# uArm_back_print.net
KiCad netlist of a schematic drawn in EAGLE
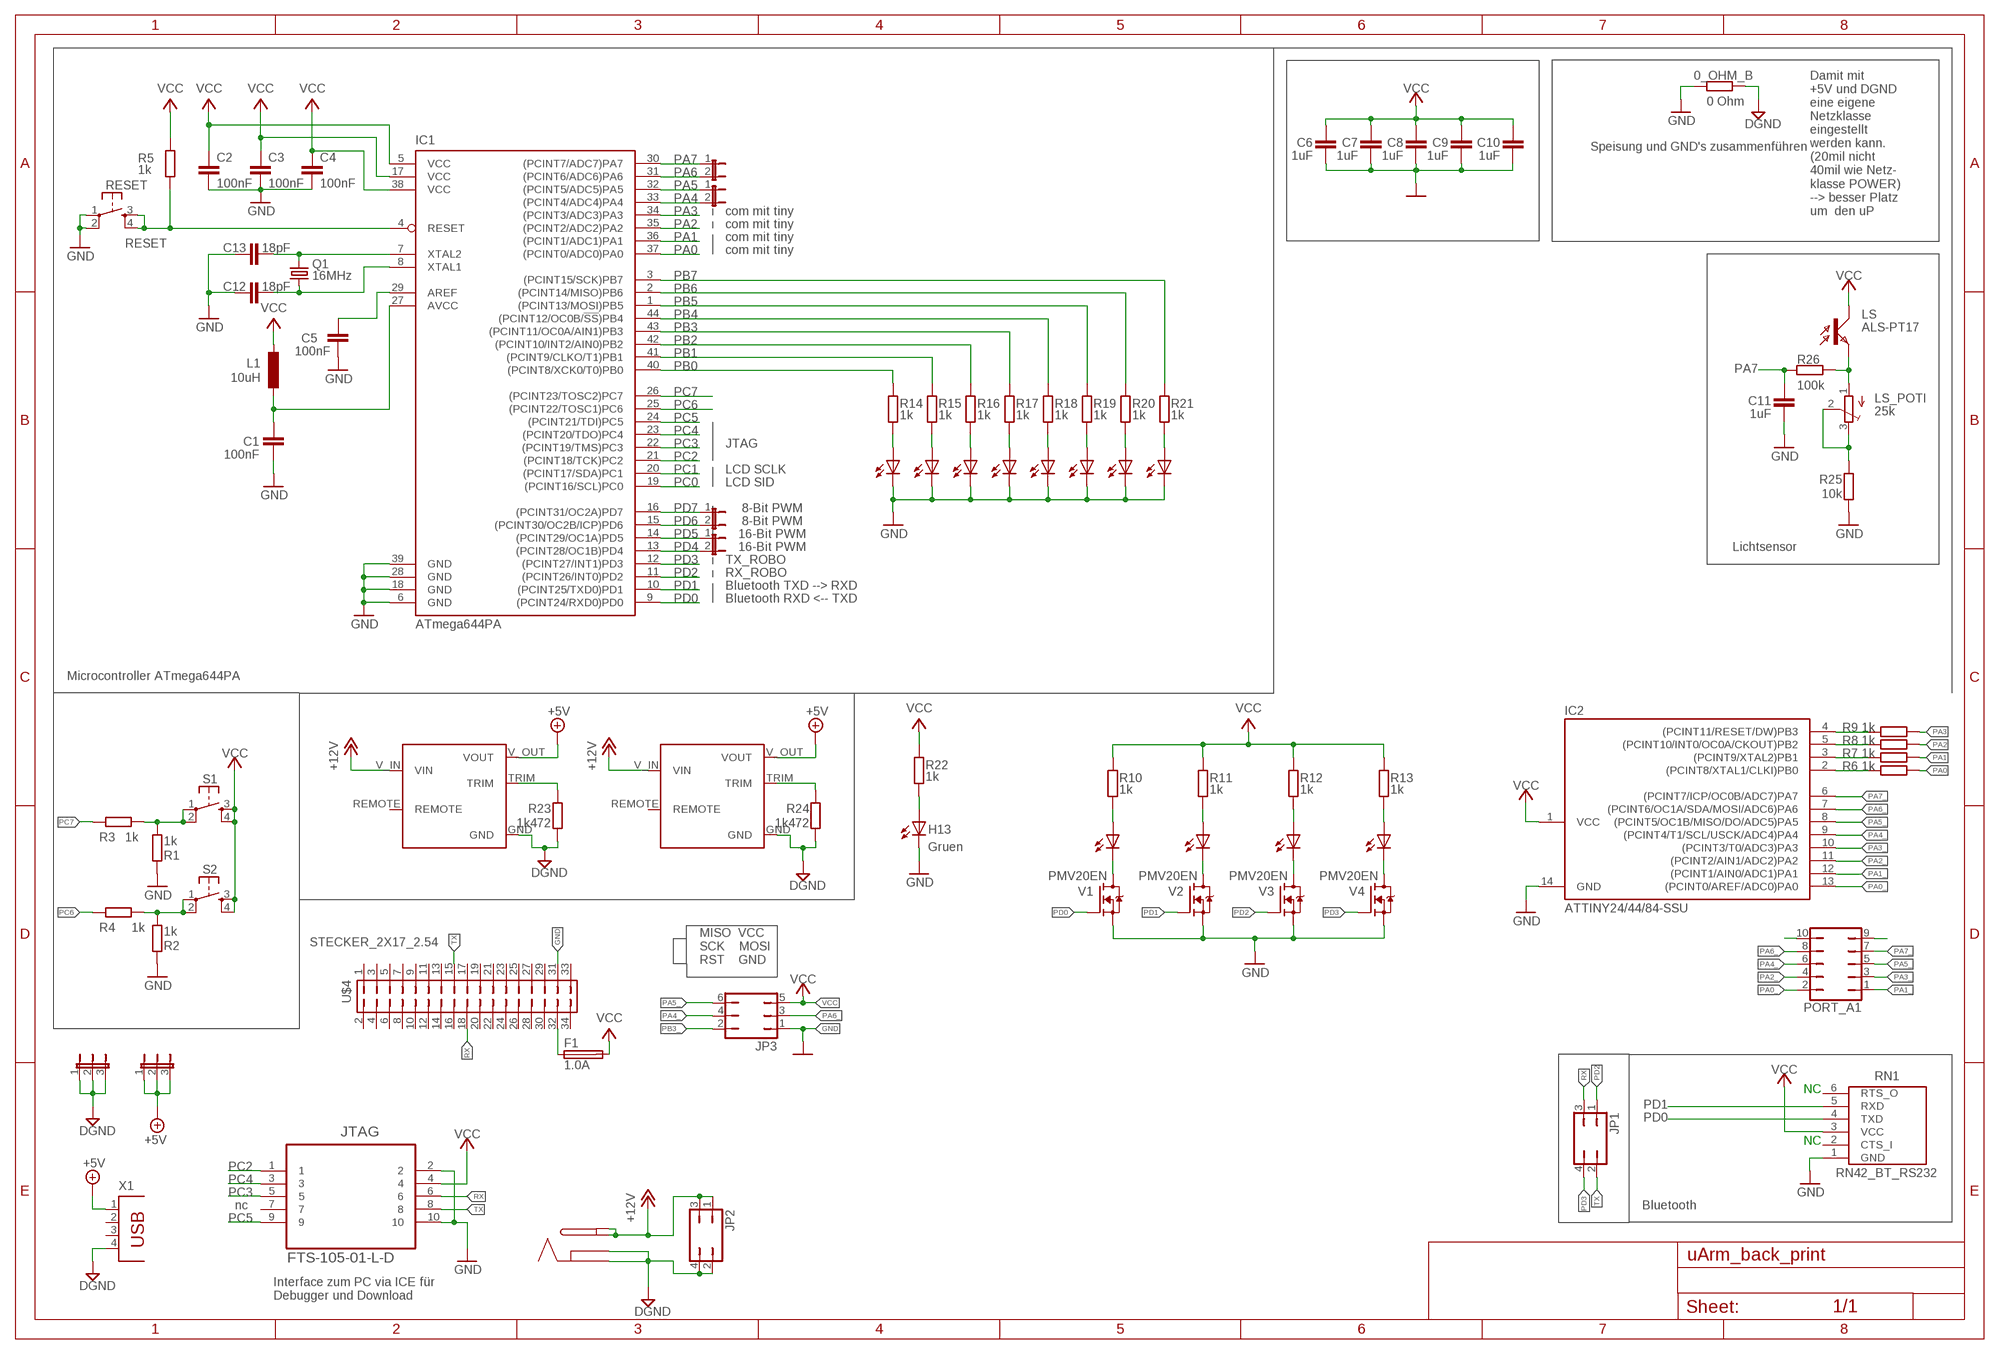
[diagram p0: schematic, sheet 1]

(export (version "E")
  (design (tool "Eeschema 10.0.6"))
  (components
    (comp (ref "0_OHM_B")
      (value "0 Ohm")
      (footprint "eagle-import:R0805")
      (libsource (lib "eagle-import") (part "R-EU_R0805"))
    )
    (comp (ref "C1")
      (value "100nF")
      (footprint "eagle-import:C0805")
      (libsource (lib "eagle-import") (part "C-EUC0805"))
    )
    (comp (ref "C2")
      (value "100nF")
      (footprint "eagle-import:C0805")
      (libsource (lib "eagle-import") (part "C-EUC0805"))
    )
    (comp (ref "C3")
      (value "100nF")
      (footprint "eagle-import:C0805")
      (libsource (lib "eagle-import") (part "C-EUC0805"))
    )
    (comp (ref "C4")
      (value "100nF")
      (footprint "eagle-import:C0805")
      (libsource (lib "eagle-import") (part "C-EUC0805"))
    )
    (comp (ref "C5")
      (value "100nF")
      (footprint "eagle-import:C0805")
      (libsource (lib "eagle-import") (part "C-EUC0805"))
    )
    (comp (ref "C6")
      (value "1uF")
      (footprint "eagle-import:C0805")
      (libsource (lib "eagle-import") (part "C-EUC0805"))
    )
    (comp (ref "C7")
      (value "1uF")
      (footprint "eagle-import:C0805")
      (libsource (lib "eagle-import") (part "C-EUC0805"))
    )
    (comp (ref "C8")
      (value "1uF")
      (footprint "eagle-import:C0805")
      (libsource (lib "eagle-import") (part "C-EUC0805"))
    )
    (comp (ref "C9")
      (value "1uF")
      (footprint "eagle-import:C0805")
      (libsource (lib "eagle-import") (part "C-EUC0805"))
    )
    (comp (ref "C10")
      (value "1uF")
      (footprint "eagle-import:C0805")
      (libsource (lib "eagle-import") (part "C-EUC0805"))
    )
    (comp (ref "C11")
      (value "1uF")
      (footprint "eagle-import:C0805")
      (libsource (lib "eagle-import") (part "C-EUC0805"))
    )
    (comp (ref "C12")
      (value "18pF")
      (footprint "eagle-import:C0805")
      (libsource (lib "eagle-import") (part "C-EUC0805"))
    )
    (comp (ref "C13")
      (value "18pF")
      (footprint "eagle-import:C0805")
      (libsource (lib "eagle-import") (part "C-EUC0805"))
    )
    (comp (ref "F1")
      (value "1.0A")
      (footprint "eagle-import:F1206")
      (libsource (lib "eagle-import") (part "195601206"))
    )
    (comp (ref "H1")
      (value "Gruen")
      (footprint "eagle-import:CHIPLED_1206")
      (libsource (lib "eagle-import") (part "LEDCHIPLED_1206"))
    )
    (comp (ref "H2")
      (value "Gruen")
      (footprint "eagle-import:CHIPLED_1206")
      (libsource (lib "eagle-import") (part "LEDCHIPLED_1206"))
    )
    (comp (ref "H3")
      (value "Gruen")
      (footprint "eagle-import:CHIPLED_1206")
      (libsource (lib "eagle-import") (part "LEDCHIPLED_1206"))
    )
    (comp (ref "H4")
      (value "Gruen")
      (footprint "eagle-import:CHIPLED_1206")
      (libsource (lib "eagle-import") (part "LEDCHIPLED_1206"))
    )
    (comp (ref "H5")
      (value "Gruen")
      (footprint "eagle-import:CHIPLED_1206")
      (libsource (lib "eagle-import") (part "LEDCHIPLED_1206"))
    )
    (comp (ref "H6")
      (value "Gruen")
      (footprint "eagle-import:CHIPLED_1206")
      (libsource (lib "eagle-import") (part "LEDCHIPLED_1206"))
    )
    (comp (ref "H7")
      (value "Gruen")
      (footprint "eagle-import:CHIPLED_1206")
      (libsource (lib "eagle-import") (part "LEDCHIPLED_1206"))
    )
    (comp (ref "H8")
      (value "Gruen")
      (footprint "eagle-import:CHIPLED_1206")
      (libsource (lib "eagle-import") (part "LEDCHIPLED_1206"))
    )
    (comp (ref "H9")
      (value "Gruen")
      (footprint "eagle-import:CHIPLED_1206")
      (libsource (lib "eagle-import") (part "LEDCHIPLED_1206"))
    )
    (comp (ref "H10")
      (value "Gruen")
      (footprint "eagle-import:CHIPLED_1206")
      (libsource (lib "eagle-import") (part "LEDCHIPLED_1206"))
    )
    (comp (ref "H11")
      (value "Gruen")
      (footprint "eagle-import:CHIPLED_1206")
      (libsource (lib "eagle-import") (part "LEDCHIPLED_1206"))
    )
    (comp (ref "H12")
      (value "Gruen")
      (footprint "eagle-import:CHIPLED_1206")
      (libsource (lib "eagle-import") (part "LEDCHIPLED_1206"))
    )
    (comp (ref "H13")
      (value "Gruen")
      (footprint "eagle-import:CHIPLED_1206")
      (libsource (lib "eagle-import") (part "LEDCHIPLED_1206"))
    )
    (comp (ref "IC1")
      (value "ATmega644PA")
      (footprint "eagle-import:TQFP44")
      (fields (field (name "MPN") "ATMEGA644PV-10AU"))
      (libsource (lib "eagle-import") (part "ATMEGA644A"))
    )
    (comp (ref "IC2")
      (value "ATTINY24/44/84-SSU")
      (footprint "eagle-import:SOIC14")
      (libsource (lib "eagle-import") (part "ATTINY24/44/84-SSU"))
    )
    (comp (ref "IC3")
      (value "DCDC")
      (footprint "eagle-import:1X2,3_2.54MM")
      (libsource (lib "eagle-import") (part "DCDC"))
    )
    (comp (ref "IC4")
      (value "DCDC")
      (footprint "eagle-import:1X2,3_2.54MM")
      (libsource (lib "eagle-import") (part "DCDC"))
    )
    (comp (ref "JP1")
      (value "JP2Q")
      (footprint "eagle-import:JP2Q")
      (libsource (lib "eagle-import") (part "JP2Q"))
    )
    (comp (ref "JP2")
      (value "JP2Q")
      (footprint "eagle-import:JP2Q")
      (libsource (lib "eagle-import") (part "JP2Q"))
    )
    (comp (ref "JP3")
      (value "JP3Q")
      (footprint "eagle-import:JP3Q")
      (libsource (lib "eagle-import") (part "JP3Q"))
    )
    (comp (ref "JP4")
      (value "JP1E")
      (footprint "eagle-import:JP1")
      (libsource (lib "eagle-import") (part "JP1E"))
    )
    (comp (ref "JP5")
      (value "JP1E")
      (footprint "eagle-import:JP1")
      (libsource (lib "eagle-import") (part "JP1E"))
    )
    (comp (ref "JP6")
      (value "JP2E")
      (footprint "eagle-import:JP2")
      (libsource (lib "eagle-import") (part "JP2E"))
    )
    (comp (ref "JP7")
      (value "JP2E")
      (footprint "eagle-import:JP2")
      (libsource (lib "eagle-import") (part "JP2E"))
    )
    (comp (ref "JP8")
      (value "JP1E")
      (footprint "eagle-import:JP1")
      (libsource (lib "eagle-import") (part "JP1E"))
    )
    (comp (ref "JP9")
      (value "JP1E")
      (footprint "eagle-import:JP1")
      (libsource (lib "eagle-import") (part "JP1E"))
    )
    (comp (ref "JTAG")
      (value "FTS-105-01-L-D")
      (footprint "eagle-import:SAMTEC_FTS-105-01-L-D")
      (libsource (lib "eagle-import") (part "FTS-105-01-L-D"))
    )
    (comp (ref "L1")
      (value "10uH")
      (footprint "eagle-import:L2825P")
      (libsource (lib "eagle-import") (part "L-EUL2825P"))
    )
    (comp (ref "LS")
      (value "ALS-PT17")
      (footprint "eagle-import:SOD232-W")
      (libsource (lib "eagle-import") (part "ALS-PT17-51C"))
    )
    (comp (ref "LS_POTI")
      (value "25k")
      (footprint "eagle-import:3223G")
      (libsource (lib "eagle-import") (part "TRIM_EU-3223G"))
    )
    (comp (ref "PORT_A1")
      (value "JP5Q")
      (footprint "eagle-import:JP5Q")
      (libsource (lib "eagle-import") (part "JP5Q"))
    )
    (comp (ref "Q1")
      (value "16MHz")
      (footprint "eagle-import:HC49UP")
      (libsource (lib "eagle-import") (part "CRYSTALHC49UP"))
    )
    (comp (ref "R1")
      (value "1k")
      (footprint "eagle-import:R0805")
      (libsource (lib "eagle-import") (part "R-EU_R0805"))
    )
    (comp (ref "R2")
      (value "1k")
      (footprint "eagle-import:R0805")
      (libsource (lib "eagle-import") (part "R-EU_R0805"))
    )
    (comp (ref "R3")
      (value "1k")
      (footprint "eagle-import:R0805")
      (libsource (lib "eagle-import") (part "R-EU_R0805"))
    )
    (comp (ref "R4")
      (value "1k")
      (footprint "eagle-import:R0805")
      (libsource (lib "eagle-import") (part "R-EU_R0805"))
    )
    (comp (ref "R5")
      (value "1k")
      (footprint "eagle-import:R0805")
      (libsource (lib "eagle-import") (part "R-EU_R0805"))
    )
    (comp (ref "R6")
      (value "1k")
      (footprint "eagle-import:R0805")
      (libsource (lib "eagle-import") (part "R-EU_R0805"))
    )
    (comp (ref "R7")
      (value "1k")
      (footprint "eagle-import:R0805")
      (libsource (lib "eagle-import") (part "R-EU_R0805"))
    )
    (comp (ref "R8")
      (value "1k")
      (footprint "eagle-import:R0805")
      (libsource (lib "eagle-import") (part "R-EU_R0805"))
    )
    (comp (ref "R9")
      (value "1k")
      (footprint "eagle-import:R0805")
      (libsource (lib "eagle-import") (part "R-EU_R0805"))
    )
    (comp (ref "R10")
      (value "1k")
      (footprint "eagle-import:R0805")
      (libsource (lib "eagle-import") (part "R-EU_R0805"))
    )
    (comp (ref "R11")
      (value "1k")
      (footprint "eagle-import:R0805")
      (libsource (lib "eagle-import") (part "R-EU_R0805"))
    )
    (comp (ref "R12")
      (value "1k")
      (footprint "eagle-import:R0805")
      (libsource (lib "eagle-import") (part "R-EU_R0805"))
    )
    (comp (ref "R13")
      (value "1k")
      (footprint "eagle-import:R0805")
      (libsource (lib "eagle-import") (part "R-EU_R0805"))
    )
    (comp (ref "R14")
      (value "1k")
      (footprint "eagle-import:R0805")
      (libsource (lib "eagle-import") (part "R-EU_R0805"))
    )
    (comp (ref "R15")
      (value "1k")
      (footprint "eagle-import:R0805")
      (libsource (lib "eagle-import") (part "R-EU_R0805"))
    )
    (comp (ref "R16")
      (value "1k")
      (footprint "eagle-import:R0805")
      (libsource (lib "eagle-import") (part "R-EU_R0805"))
    )
    (comp (ref "R17")
      (value "1k")
      (footprint "eagle-import:R0805")
      (libsource (lib "eagle-import") (part "R-EU_R0805"))
    )
    (comp (ref "R18")
      (value "1k")
      (footprint "eagle-import:R0805")
      (libsource (lib "eagle-import") (part "R-EU_R0805"))
    )
    (comp (ref "R19")
      (value "1k")
      (footprint "eagle-import:R0805")
      (libsource (lib "eagle-import") (part "R-EU_R0805"))
    )
    (comp (ref "R20")
      (value "1k")
      (footprint "eagle-import:R0805")
      (libsource (lib "eagle-import") (part "R-EU_R0805"))
    )
    (comp (ref "R21")
      (value "1k")
      (footprint "eagle-import:R0805")
      (libsource (lib "eagle-import") (part "R-EU_R0805"))
    )
    (comp (ref "R22")
      (value "1k")
      (footprint "eagle-import:R0805")
      (libsource (lib "eagle-import") (part "R-EU_R0805"))
    )
    (comp (ref "R23")
      (value "1k472")
      (footprint "eagle-import:R0805")
      (libsource (lib "eagle-import") (part "R-EU_R0805"))
    )
    (comp (ref "R24")
      (value "1k472")
      (footprint "eagle-import:R0805")
      (libsource (lib "eagle-import") (part "R-EU_R0805"))
    )
    (comp (ref "R25")
      (value "10k")
      (footprint "eagle-import:R0805")
      (libsource (lib "eagle-import") (part "R-EU_R0805"))
    )
    (comp (ref "R26")
      (value "100k")
      (footprint "eagle-import:R0805")
      (libsource (lib "eagle-import") (part "R-EU_R0805"))
    )
    (comp (ref "RESET")
      (value "TS42_4PAD")
      (footprint "eagle-import:TS42_4PAD")
      (libsource (lib "eagle-import") (part "TS42_4PAD"))
    )
    (comp (ref "RN1")
      (value "RN42_BT_RS232")
      (footprint "eagle-import:RN42BT_RS232")
      (libsource (lib "eagle-import") (part "RN42_BT_RS232"))
    )
    (comp (ref "S1")
      (value "TS42_4PAD")
      (footprint "eagle-import:TS42_4PAD")
      (libsource (lib "eagle-import") (part "TS42_4PAD"))
    )
    (comp (ref "S2")
      (value "TS42_4PAD")
      (footprint "eagle-import:TS42_4PAD")
      (libsource (lib "eagle-import") (part "TS42_4PAD"))
    )
    (comp (ref "U$1")
      (value "BUCHSE")
      (footprint "eagle-import:BUCHSE")
      (libsource (lib "eagle-import") (part "BUCHSE"))
    )
    (comp (ref "U$4")
      (value "STECKER_2X17_2.54")
      (footprint "eagle-import:2X17_2.54")
      (libsource (lib "eagle-import") (part "STECKER_2X17_2.54"))
    )
    (comp (ref "V1")
      (value "PMV20EN")
      (footprint "eagle-import:SOT23")
      (libsource (lib "eagle-import") (part "BSS138"))
    )
    (comp (ref "V2")
      (value "PMV20EN")
      (footprint "eagle-import:SOT23")
      (libsource (lib "eagle-import") (part "BSS138"))
    )
    (comp (ref "V3")
      (value "PMV20EN")
      (footprint "eagle-import:SOT23")
      (libsource (lib "eagle-import") (part "BSS138"))
    )
    (comp (ref "V4")
      (value "PMV20EN")
      (footprint "eagle-import:SOT23")
      (libsource (lib "eagle-import") (part "BSS138"))
    )
    (comp (ref "X1")
      (value "PN87520")
      (footprint "eagle-import:PN87520")
      (libsource (lib "eagle-import") (part "PN87520"))
    )
  )
  (nets
    (net (code "1") (name "+5V") (class "Default")
      (node (ref "IC3") (pin "V_OUT") (pinfunction "VOUT_V_OUT") (pintype "bidirectional"))
      (node (ref "IC4") (pin "V_OUT") (pinfunction "VOUT_V_OUT") (pintype "bidirectional"))
      (node (ref "JP6") (pin "1") (pinfunction "1_1") (pintype "passive"))
      (node (ref "JP6") (pin "2") (pinfunction "2_2") (pintype "passive"))
      (node (ref "JP6") (pin "3") (pinfunction "3_3") (pintype "passive"))
      (node (ref "X1") (pin "1") (pinfunction "1_1") (pintype "passive"))
    )
    (net (code "2") (name "+12V") (class "Default")
      (node (ref "IC3") (pin "V_IN") (pinfunction "VIN_V_IN") (pintype "bidirectional"))
      (node (ref "IC4") (pin "V_IN") (pinfunction "VIN_V_IN") (pintype "bidirectional"))
      (node (ref "JP2") (pin "1") (pinfunction "1_1") (pintype "passive"))
      (node (ref "JP2") (pin "3") (pinfunction "3_3") (pintype "passive"))
      (node (ref "U$1") (pin "3") (pinfunction "3_3") (pintype "bidirectional"))
      (node (ref "U$1") (pin "3.1") (pinfunction "3.1_3.1") (pintype "bidirectional"))
    )
    (net (code "3") (name "/PA4") (class "Default")
      (node (ref "IC1") (pin "33") (pinfunction "(PCINT4/ADC4)PA4_33") (pintype "bidirectional"))
      (node (ref "JP9") (pin "2") (pinfunction "2_2") (pintype "passive"))
    )
    (net (code "4") (name "/PA5") (class "Default")
      (node (ref "IC1") (pin "32") (pinfunction "(PCINT5/ADC5)PA5_32") (pintype "bidirectional"))
      (node (ref "JP9") (pin "1") (pinfunction "1_1") (pintype "passive"))
    )
    (net (code "5") (name "/PA6") (class "Default")
      (node (ref "IC1") (pin "31") (pinfunction "(PCINT6/ADC6)PA6_31") (pintype "bidirectional"))
      (node (ref "JP8") (pin "2") (pinfunction "2_2") (pintype "passive"))
    )
    (net (code "6") (name "/PA7") (class "Default")
      (node (ref "C11") (pin "2") (pinfunction "2_2") (pintype "passive"))
      (node (ref "IC1") (pin "30") (pinfunction "(PCINT7/ADC7)PA7_30") (pintype "bidirectional"))
      (node (ref "JP8") (pin "1") (pinfunction "1_1") (pintype "passive"))
      (node (ref "R26") (pin "1") (pinfunction "1_1") (pintype "passive"))
    )
    (net (code "7") (name "/PB0") (class "Default")
      (node (ref "IC1") (pin "40") (pinfunction "(PCINT8/XCK0/T0)PB0_40") (pintype "bidirectional"))
      (node (ref "R14") (pin "2") (pinfunction "2_2") (pintype "passive"))
    )
    (net (code "8") (name "/PB1") (class "Default")
      (node (ref "IC1") (pin "41") (pinfunction "(PCINT9/CLKO/T1)PB1_41") (pintype "bidirectional"))
      (node (ref "R15") (pin "2") (pinfunction "2_2") (pintype "passive"))
    )
    (net (code "9") (name "/PB2") (class "Default")
      (node (ref "IC1") (pin "42") (pinfunction "(PCINT10/INT2/AIN0)PB2_42") (pintype "bidirectional"))
      (node (ref "R16") (pin "2") (pinfunction "2_2") (pintype "passive"))
    )
    (net (code "10") (name "/PB3") (class "Default")
      (node (ref "IC1") (pin "43") (pinfunction "(PCINT11/OC0A/AIN1)PB3_43") (pintype "bidirectional"))
      (node (ref "R17") (pin "2") (pinfunction "2_2") (pintype "passive"))
    )
    (net (code "11") (name "/PB4") (class "Default")
      (node (ref "IC1") (pin "44") (pinfunction "(PCINT12/OC0B/~{SS})PB4_44") (pintype "bidirectional"))
      (node (ref "R18") (pin "2") (pinfunction "2_2") (pintype "passive"))
    )
    (net (code "12") (name "/PB5") (class "Default")
      (node (ref "IC1") (pin "1") (pinfunction "(PCINT13/MOSI)PB5_1") (pintype "bidirectional"))
      (node (ref "R19") (pin "2") (pinfunction "2_2") (pintype "passive"))
    )
    (net (code "13") (name "/PB6") (class "Default")
      (node (ref "IC1") (pin "2") (pinfunction "(PCINT14/MISO)PB6_2") (pintype "bidirectional"))
      (node (ref "R20") (pin "2") (pinfunction "2_2") (pintype "passive"))
    )
    (net (code "14") (name "/PB7") (class "Default")
      (node (ref "IC1") (pin "3") (pinfunction "(PCINT15/SCK)PB7_3") (pintype "bidirectional"))
      (node (ref "R21") (pin "2") (pinfunction "2_2") (pintype "passive"))
    )
    (net (code "15") (name "/PC0") (class "Default")
      (node (ref "IC1") (pin "19") (pinfunction "(PCINT16/SCL)PC0_19") (pintype "output"))
    )
    (net (code "16") (name "/PC1") (class "Default")
      (node (ref "IC1") (pin "20") (pinfunction "(PCINT17/SDA)PC1_20") (pintype "output"))
    )
    (net (code "17") (name "/PC2") (class "Default")
      (node (ref "IC1") (pin "21") (pinfunction "(PCINT18/TCK)PC2_21") (pintype "output"))
      (node (ref "JTAG") (pin "1") (pinfunction "1_1") (pintype "passive"))
    )
    (net (code "18") (name "/PC3") (class "Default")
      (node (ref "IC1") (pin "22") (pinfunction "(PCINT19/TMS)PC3_22") (pintype "output"))
      (node (ref "JTAG") (pin "5") (pinfunction "5_5") (pintype "passive"))
    )
    (net (code "19") (name "/PC4") (class "Default")
      (node (ref "IC1") (pin "23") (pinfunction "(PCINT20/TDO)PC4_23") (pintype "output"))
      (node (ref "JTAG") (pin "3") (pinfunction "3_3") (pintype "passive"))
    )
    (net (code "20") (name "/PC5") (class "Default")
      (node (ref "IC1") (pin "24") (pinfunction "(PCINT21/TDI)PC5_24") (pintype "output"))
      (node (ref "JTAG") (pin "9") (pinfunction "9_9") (pintype "passive"))
    )
    (net (code "21") (name "/PD4") (class "Default")
      (node (ref "IC1") (pin "13") (pinfunction "(PCINT28/OC1B)PD4_13") (pintype "bidirectional"))
      (node (ref "JP4") (pin "2") (pinfunction "2_2") (pintype "passive"))
    )
    (net (code "22") (name "/PD5") (class "Default")
      (node (ref "IC1") (pin "14") (pinfunction "(PCINT29/OC1A)PD5_14") (pintype "bidirectional"))
      (node (ref "JP4") (pin "1") (pinfunction "1_1") (pintype "passive"))
    )
    (net (code "23") (name "/PD6") (class "Default")
      (node (ref "IC1") (pin "15") (pinfunction "(PCINT30/OC2B/ICP)PD6_15") (pintype "bidirectional"))
      (node (ref "JP5") (pin "2") (pinfunction "2_2") (pintype "passive"))
    )
    (net (code "24") (name "/PD7") (class "Default")
      (node (ref "IC1") (pin "16") (pinfunction "(PCINT31/OC2A)PD7_16") (pintype "bidirectional"))
      (node (ref "JP5") (pin "1") (pinfunction "1_1") (pintype "passive"))
    )
    (net (code "25") (name "/RESET") (class "Default")
      (node (ref "IC1") (pin "4") (pinfunction "RESET_4") (pintype "input"))
      (node (ref "R5") (pin "1") (pinfunction "1_1") (pintype "passive"))
      (node (ref "RESET") (pin "3") (pinfunction "3_3") (pintype "passive"))
      (node (ref "RESET") (pin "4") (pinfunction "4_4") (pintype "passive"))
    )
    (net (code "26") (name "DGND") (class "Default")
      (node (ref "0_OHM_B") (pin "2") (pinfunction "2_2") (pintype "passive"))
      (node (ref "IC3") (pin "GND") (pinfunction "GND_GND") (pintype "bidirectional"))
      (node (ref "IC4") (pin "GND") (pinfunction "GND_GND") (pintype "bidirectional"))
      (node (ref "JP2") (pin "2") (pinfunction "2_2") (pintype "passive"))
      (node (ref "JP2") (pin "4") (pinfunction "4_4") (pintype "passive"))
      (node (ref "JP7") (pin "1") (pinfunction "1_1") (pintype "passive"))
      (node (ref "JP7") (pin "2") (pinfunction "2_2") (pintype "passive"))
      (node (ref "JP7") (pin "3") (pinfunction "3_3") (pintype "passive"))
      (node (ref "R23") (pin "1") (pinfunction "1_1") (pintype "passive"))
      (node (ref "R24") (pin "1") (pinfunction "1_1") (pintype "passive"))
      (node (ref "U$1") (pin "1") (pinfunction "1_1") (pintype "bidirectional"))
      (node (ref "U$1") (pin "2") (pinfunction "2_2") (pintype "bidirectional"))
      (node (ref "X1") (pin "4") (pinfunction "4_4") (pintype "passive"))
    )
    (net (code "27") (name "GND") (class "Default")
      (node (ref "0_OHM_B") (pin "1") (pinfunction "1_1") (pintype "passive"))
      (node (ref "C1") (pin "1") (pinfunction "1_1") (pintype "passive"))
      (node (ref "C10") (pin "1") (pinfunction "1_1") (pintype "passive"))
      (node (ref "C11") (pin "1") (pinfunction "1_1") (pintype "passive"))
      (node (ref "C12") (pin "2") (pinfunction "2_2") (pintype "passive"))
      (node (ref "C13") (pin "1") (pinfunction "1_1") (pintype "passive"))
      (node (ref "C2") (pin "2") (pinfunction "2_2") (pintype "passive"))
      (node (ref "C3") (pin "2") (pinfunction "2_2") (pintype "passive"))
      (node (ref "C4") (pin "2") (pinfunction "2_2") (pintype "passive"))
      (node (ref "C5") (pin "1") (pinfunction "1_1") (pintype "passive"))
      (node (ref "C6") (pin "1") (pinfunction "1_1") (pintype "passive"))
      (node (ref "C7") (pin "1") (pinfunction "1_1") (pintype "passive"))
      (node (ref "C8") (pin "1") (pinfunction "1_1") (pintype "passive"))
      (node (ref "C9") (pin "1") (pinfunction "1_1") (pintype "passive"))
      (node (ref "H1") (pin "C") (pinfunction "C_C") (pintype "passive"))
      (node (ref "H13") (pin "C") (pinfunction "C_C") (pintype "passive"))
      (node (ref "H2") (pin "C") (pinfunction "C_C") (pintype "passive"))
      (node (ref "H3") (pin "C") (pinfunction "C_C") (pintype "passive"))
      (node (ref "H4") (pin "C") (pinfunction "C_C") (pintype "passive"))
      (node (ref "H5") (pin "C") (pinfunction "C_C") (pintype "passive"))
      (node (ref "H6") (pin "C") (pinfunction "C_C") (pintype "passive"))
      (node (ref "H7") (pin "C") (pinfunction "C_C") (pintype "passive"))
      (node (ref "H8") (pin "C") (pinfunction "C_C") (pintype "passive"))
      (node (ref "IC1") (pin "18") (pinfunction "GND_18") (pintype "power_in"))
      (node (ref "IC1") (pin "28") (pinfunction "GND_28") (pintype "power_in"))
      (node (ref "IC1") (pin "39") (pinfunction "GND_39") (pintype "power_in"))
      (node (ref "IC1") (pin "6") (pinfunction "GND_6") (pintype "power_in"))
      (node (ref "IC2") (pin "14") (pinfunction "GND_14") (pintype "power_in"))
      (node (ref "JP3") (pin "1") (pinfunction "1_1") (pintype "passive"))
      (node (ref "JTAG") (pin "10") (pinfunction "10_10") (pintype "passive"))
      (node (ref "JTAG") (pin "2") (pinfunction "2_2") (pintype "passive"))
      (node (ref "R1") (pin "1") (pinfunction "1_1") (pintype "passive"))
      (node (ref "R2") (pin "1") (pinfunction "1_1") (pintype "passive"))
      (node (ref "R25") (pin "1") (pinfunction "1_1") (pintype "passive"))
      (node (ref "RESET") (pin "1") (pinfunction "1_1") (pintype "passive"))
      (node (ref "RESET") (pin "2") (pinfunction "2_2") (pintype "passive"))
      (node (ref "RN1") (pin "1") (pinfunction "GND_1") (pintype "bidirectional"))
      (node (ref "U$4") (pin "31") (pinfunction "31_31") (pintype "passive"))
      (node (ref "V1") (pin "2") (pinfunction "S_2") (pintype "passive"))
      (node (ref "V2") (pin "2") (pinfunction "S_2") (pintype "passive"))
      (node (ref "V3") (pin "2") (pinfunction "S_2") (pintype "passive"))
      (node (ref "V4") (pin "2") (pinfunction "S_2") (pintype "passive"))
    )
    (net (code "28") (name "Net-(F1-Pad1)") (class "Default")
      (node (ref "F1") (pin "1") (pinfunction "1_1") (pintype "passive"))
      (node (ref "U$4") (pin "32") (pinfunction "32_32") (pintype "passive"))
    )
    (net (code "29") (name "Net-(H1-PadA)") (class "Default")
      (node (ref "H1") (pin "A") (pinfunction "A_A") (pintype "passive"))
      (node (ref "R14") (pin "1") (pinfunction "1_1") (pintype "passive"))
    )
    (net (code "30") (name "Net-(H2-PadA)") (class "Default")
      (node (ref "H2") (pin "A") (pinfunction "A_A") (pintype "passive"))
      (node (ref "R15") (pin "1") (pinfunction "1_1") (pintype "passive"))
    )
    (net (code "31") (name "Net-(H3-PadA)") (class "Default")
      (node (ref "H3") (pin "A") (pinfunction "A_A") (pintype "passive"))
      (node (ref "R16") (pin "1") (pinfunction "1_1") (pintype "passive"))
    )
    (net (code "32") (name "Net-(H4-PadA)") (class "Default")
      (node (ref "H4") (pin "A") (pinfunction "A_A") (pintype "passive"))
      (node (ref "R17") (pin "1") (pinfunction "1_1") (pintype "passive"))
    )
    (net (code "33") (name "Net-(H5-PadA)") (class "Default")
      (node (ref "H5") (pin "A") (pinfunction "A_A") (pintype "passive"))
      (node (ref "R18") (pin "1") (pinfunction "1_1") (pintype "passive"))
    )
    (net (code "34") (name "Net-(H6-PadA)") (class "Default")
      (node (ref "H6") (pin "A") (pinfunction "A_A") (pintype "passive"))
      (node (ref "R19") (pin "1") (pinfunction "1_1") (pintype "passive"))
    )
    (net (code "35") (name "Net-(H7-PadA)") (class "Default")
      (node (ref "H7") (pin "A") (pinfunction "A_A") (pintype "passive"))
      (node (ref "R20") (pin "1") (pinfunction "1_1") (pintype "passive"))
    )
    (net (code "36") (name "Net-(H8-PadA)") (class "Default")
      (node (ref "H8") (pin "A") (pinfunction "A_A") (pintype "passive"))
      (node (ref "R21") (pin "1") (pinfunction "1_1") (pintype "passive"))
    )
    (net (code "37") (name "Net-(H9-PadA)") (class "Default")
      (node (ref "H9") (pin "A") (pinfunction "A_A") (pintype "passive"))
      (node (ref "R10") (pin "1") (pinfunction "1_1") (pintype "passive"))
    )
    (net (code "38") (name "Net-(H10-PadA)") (class "Default")
      (node (ref "H10") (pin "A") (pinfunction "A_A") (pintype "passive"))
      (node (ref "R11") (pin "1") (pinfunction "1_1") (pintype "passive"))
    )
    (net (code "39") (name "Net-(H11-PadA)") (class "Default")
      (node (ref "H11") (pin "A") (pinfunction "A_A") (pintype "passive"))
      (node (ref "R12") (pin "1") (pinfunction "1_1") (pintype "passive"))
    )
    (net (code "40") (name "Net-(H12-PadA)") (class "Default")
      (node (ref "H12") (pin "A") (pinfunction "A_A") (pintype "passive"))
      (node (ref "R13") (pin "1") (pinfunction "1_1") (pintype "passive"))
    )
    (net (code "41") (name "Net-(H13-PadA)") (class "Default")
      (node (ref "H13") (pin "A") (pinfunction "A_A") (pintype "passive"))
      (node (ref "R22") (pin "1") (pinfunction "1_1") (pintype "passive"))
    )
    (net (code "42") (name "Net-(IC1-AREF)") (class "Default")
      (node (ref "C5") (pin "2") (pinfunction "2_2") (pintype "passive"))
      (node (ref "IC1") (pin "29") (pinfunction "AREF_29") (pintype "passive"))
    )
    (net (code "43") (name "Net-(IC1-AVCC)") (class "Default")
      (node (ref "C1") (pin "2") (pinfunction "2_2") (pintype "passive"))
      (node (ref "IC1") (pin "27") (pinfunction "AVCC_27") (pintype "passive"))
      (node (ref "L1") (pin "2") (pinfunction "2_2") (pintype "passive"))
    )
    (net (code "44") (name "Net-(IC1-XTAL1)") (class "Default")
      (node (ref "C12") (pin "1") (pinfunction "1_1") (pintype "passive"))
      (node (ref "IC1") (pin "8") (pinfunction "XTAL1_8") (pintype "bidirectional"))
      (node (ref "Q1") (pin "1") (pinfunction "1_1") (pintype "passive"))
    )
    (net (code "45") (name "Net-(IC1-XTAL2)") (class "Default")
      (node (ref "C13") (pin "2") (pinfunction "2_2") (pintype "passive"))
      (node (ref "IC1") (pin "7") (pinfunction "XTAL2_7") (pintype "bidirectional"))
      (node (ref "Q1") (pin "2") (pinfunction "2_2") (pintype "passive"))
    )
    (net (code "46") (name "Net-(IC2-(PCINT8{slash}XTAL1{slash}CLKI)PB0)") (class "Default")
      (node (ref "IC2") (pin "2") (pinfunction "(PCINT8/XTAL1/CLKI)PB0_2") (pintype "bidirectional"))
      (node (ref "R6") (pin "2") (pinfunction "2_2") (pintype "passive"))
    )
    (net (code "47") (name "Net-(IC2-(PCINT9{slash}XTAL2)PB1)") (class "Default")
      (node (ref "IC2") (pin "3") (pinfunction "(PCINT9/XTAL2)PB1_3") (pintype "bidirectional"))
      (node (ref "R7") (pin "2") (pinfunction "2_2") (pintype "passive"))
    )
    (net (code "48") (name "Net-(IC2-(PCINT10{slash}INT0{slash}OC0A{slash}CKOUT)PB2)") (class "Default")
      (node (ref "IC2") (pin "5") (pinfunction "(PCINT10/INT0/OC0A/CKOUT)PB2_5") (pintype "bidirectional"))
      (node (ref "R8") (pin "2") (pinfunction "2_2") (pintype "passive"))
    )
    (net (code "49") (name "Net-(IC3-PadTRIM)") (class "Default")
      (node (ref "IC3") (pin "TRIM") (pinfunction "TRIM_TRIM") (pintype "bidirectional"))
      (node (ref "R23") (pin "2") (pinfunction "2_2") (pintype "passive"))
    )
    (net (code "50") (name "Net-(IC4-PadTRIM)") (class "Default")
      (node (ref "IC4") (pin "TRIM") (pinfunction "TRIM_TRIM") (pintype "bidirectional"))
      (node (ref "R24") (pin "2") (pinfunction "2_2") (pintype "passive"))
    )
    (net (code "51") (name "Net-(LS_POTI-A)") (class "Default")
      (node (ref "LS") (pin "E") (pinfunction "E_E") (pintype "passive"))
      (node (ref "LS_POTI") (pin "1") (pinfunction "A_1") (pintype "passive"))
      (node (ref "R26") (pin "2") (pinfunction "2_2") (pintype "passive"))
    )
    (net (code "52") (name "Net-(LS_POTI-E)") (class "Default")
      (node (ref "LS_POTI") (pin "2") (pinfunction "S_2") (pintype "passive"))
      (node (ref "LS_POTI") (pin "3") (pinfunction "E_3") (pintype "passive"))
      (node (ref "R25") (pin "2") (pinfunction "2_2") (pintype "passive"))
    )
    (net (code "53") (name "Net-(R1-Pad2)") (class "Default")
      (node (ref "R1") (pin "2") (pinfunction "2_2") (pintype "passive"))
      (node (ref "R3") (pin "2") (pinfunction "2_2") (pintype "passive"))
      (node (ref "S1") (pin "1") (pinfunction "1_1") (pintype "passive"))
      (node (ref "S1") (pin "2") (pinfunction "2_2") (pintype "passive"))
    )
    (net (code "54") (name "Net-(R2-Pad2)") (class "Default")
      (node (ref "R2") (pin "2") (pinfunction "2_2") (pintype "passive"))
      (node (ref "R4") (pin "2") (pinfunction "2_2") (pintype "passive"))
      (node (ref "S2") (pin "1") (pinfunction "1_1") (pintype "passive"))
      (node (ref "S2") (pin "2") (pinfunction "2_2") (pintype "passive"))
    )
    (net (code "55") (name "Net-(V1-D)") (class "Default")
      (node (ref "H9") (pin "C") (pinfunction "C_C") (pintype "passive"))
      (node (ref "V1") (pin "3") (pinfunction "D_3") (pintype "passive"))
    )
    (net (code "56") (name "Net-(V2-D)") (class "Default")
      (node (ref "H10") (pin "C") (pinfunction "C_C") (pintype "passive"))
      (node (ref "V2") (pin "3") (pinfunction "D_3") (pintype "passive"))
    )
    (net (code "57") (name "Net-(V3-D)") (class "Default")
      (node (ref "H11") (pin "C") (pinfunction "C_C") (pintype "passive"))
      (node (ref "V3") (pin "3") (pinfunction "D_3") (pintype "passive"))
    )
    (net (code "58") (name "Net-(V4-D)") (class "Default")
      (node (ref "H12") (pin "C") (pinfunction "C_C") (pintype "passive"))
      (node (ref "V4") (pin "3") (pinfunction "D_3") (pintype "passive"))
    )
    (net (code "59") (name "PA0") (class "Default")
      (node (ref "IC1") (pin "37") (pinfunction "(PCINT0/ADC0)PA0_37") (pintype "bidirectional"))
      (node (ref "R6") (pin "1") (pinfunction "1_1") (pintype "passive"))
    )
    (net (code "60") (name "PA0_") (class "Default")
      (node (ref "IC2") (pin "13") (pinfunction "(PCINT0/AREF/ADC0)PA0_13") (pintype "bidirectional"))
      (node (ref "PORT_A1") (pin "2") (pinfunction "2_2") (pintype "passive"))
    )
    (net (code "61") (name "PA1") (class "Default")
      (node (ref "IC1") (pin "36") (pinfunction "(PCINT1/ADC1)PA1_36") (pintype "bidirectional"))
      (node (ref "R7") (pin "1") (pinfunction "1_1") (pintype "passive"))
    )
    (net (code "62") (name "PA1_") (class "Default")
      (node (ref "IC2") (pin "12") (pinfunction "(PCINT1/AIN0/ADC1)PA1_12") (pintype "bidirectional"))
      (node (ref "PORT_A1") (pin "1") (pinfunction "1_1") (pintype "passive"))
    )
    (net (code "63") (name "PA2") (class "Default")
      (node (ref "IC1") (pin "35") (pinfunction "(PCINT2/ADC2)PA2_35") (pintype "bidirectional"))
      (node (ref "R8") (pin "1") (pinfunction "1_1") (pintype "passive"))
    )
    (net (code "64") (name "PA2_") (class "Default")
      (node (ref "IC2") (pin "11") (pinfunction "(PCINT2/AIN1/ADC2)PA2_11") (pintype "bidirectional"))
      (node (ref "PORT_A1") (pin "4") (pinfunction "4_4") (pintype "passive"))
    )
    (net (code "65") (name "PA3") (class "Default")
      (node (ref "IC1") (pin "34") (pinfunction "(PCINT3/ADC3)PA3_34") (pintype "bidirectional"))
      (node (ref "R9") (pin "1") (pinfunction "1_1") (pintype "passive"))
    )
    (net (code "66") (name "PA3_") (class "Default")
      (node (ref "IC2") (pin "10") (pinfunction "(PCINT3/T0/ADC3)PA3_10") (pintype "bidirectional"))
      (node (ref "PORT_A1") (pin "3") (pinfunction "3_3") (pintype "passive"))
    )
    (net (code "67") (name "PA4_") (class "Default")
      (node (ref "IC2") (pin "9") (pinfunction "(PCINT4/T1/SCL/USCK/ADC4)PA4_9") (pintype "bidirectional"))
      (node (ref "JP3") (pin "4") (pinfunction "4_4") (pintype "passive"))
      (node (ref "PORT_A1") (pin "6") (pinfunction "6_6") (pintype "passive"))
    )
    (net (code "68") (name "PA5_") (class "Default")
      (node (ref "IC2") (pin "8") (pinfunction "(PCINT5/OC1B/MISO/DO/ADC5)PA5_8") (pintype "bidirectional"))
      (node (ref "JP3") (pin "6") (pinfunction "6_6") (pintype "passive"))
      (node (ref "PORT_A1") (pin "5") (pinfunction "5_5") (pintype "passive"))
    )
    (net (code "69") (name "PA6_") (class "Default")
      (node (ref "IC2") (pin "7") (pinfunction "(PCINT6/OC1A/SDA/MOSI/ADC6)PA6_7") (pintype "bidirectional"))
      (node (ref "JP3") (pin "3") (pinfunction "3_3") (pintype "passive"))
      (node (ref "PORT_A1") (pin "8") (pinfunction "8_8") (pintype "passive"))
    )
    (net (code "70") (name "PA7_") (class "Default")
      (node (ref "IC2") (pin "6") (pinfunction "(PCINT7/ICP/OC0B/ADC7)PA7_6") (pintype "bidirectional"))
      (node (ref "PORT_A1") (pin "7") (pinfunction "7_7") (pintype "passive"))
    )
    (net (code "71") (name "PB3_") (class "Default")
      (node (ref "IC2") (pin "4") (pinfunction "(PCINT11/RESET/DW)PB3_4") (pintype "bidirectional"))
      (node (ref "JP3") (pin "2") (pinfunction "2_2") (pintype "passive"))
      (node (ref "R9") (pin "2") (pinfunction "2_2") (pintype "passive"))
    )
    (net (code "72") (name "PC6") (class "Default")
      (node (ref "IC1") (pin "25") (pinfunction "(PCINT22/TOSC1)PC6_25") (pintype "output"))
      (node (ref "R4") (pin "1") (pinfunction "1_1") (pintype "passive"))
    )
    (net (code "73") (name "PC7") (class "Default")
      (node (ref "IC1") (pin "26") (pinfunction "(PCINT23/TOSC2)PC7_26") (pintype "output"))
      (node (ref "R3") (pin "1") (pinfunction "1_1") (pintype "passive"))
    )
    (net (code "74") (name "PD0") (class "Default")
      (node (ref "IC1") (pin "9") (pinfunction "(PCINT24/RXD0)PD0_9") (pintype "bidirectional"))
      (node (ref "RN1") (pin "4") (pinfunction "TXD_4") (pintype "bidirectional"))
      (node (ref "V1") (pin "1") (pinfunction "G_1") (pintype "passive"))
    )
    (net (code "75") (name "PD1") (class "Default")
      (node (ref "IC1") (pin "10") (pinfunction "(PCINT25/TXD0)PD1_10") (pintype "bidirectional"))
      (node (ref "RN1") (pin "5") (pinfunction "RXD_5") (pintype "bidirectional"))
      (node (ref "V2") (pin "1") (pinfunction "G_1") (pintype "passive"))
    )
    (net (code "76") (name "PD2") (class "Default")
      (node (ref "IC1") (pin "11") (pinfunction "(PCINT26/INT0)PD2_11") (pintype "bidirectional"))
      (node (ref "JP1") (pin "1") (pinfunction "1_1") (pintype "passive"))
      (node (ref "V3") (pin "1") (pinfunction "G_1") (pintype "passive"))
    )
    (net (code "77") (name "PD3") (class "Default")
      (node (ref "IC1") (pin "12") (pinfunction "(PCINT27/INT1)PD3_12") (pintype "bidirectional"))
      (node (ref "JP1") (pin "4") (pinfunction "4_4") (pintype "passive"))
      (node (ref "V4") (pin "1") (pinfunction "G_1") (pintype "passive"))
    )
    (net (code "78") (name "RX") (class "Default")
      (node (ref "JP1") (pin "3") (pinfunction "3_3") (pintype "passive"))
      (node (ref "JTAG") (pin "6") (pinfunction "6_6") (pintype "passive"))
      (node (ref "U$4") (pin "18") (pinfunction "18_18") (pintype "passive"))
    )
    (net (code "79") (name "TX") (class "Default")
      (node (ref "JP1") (pin "2") (pinfunction "2_2") (pintype "passive"))
      (node (ref "JTAG") (pin "8") (pinfunction "8_8") (pintype "passive"))
      (node (ref "U$4") (pin "15") (pinfunction "15_15") (pintype "passive"))
    )
    (net (code "80") (name "VCC") (class "Default")
      (node (ref "C10") (pin "2") (pinfunction "2_2") (pintype "passive"))
      (node (ref "C2") (pin "1") (pinfunction "1_1") (pintype "passive"))
      (node (ref "C3") (pin "1") (pinfunction "1_1") (pintype "passive"))
      (node (ref "C4") (pin "1") (pinfunction "1_1") (pintype "passive"))
      (node (ref "C6") (pin "2") (pinfunction "2_2") (pintype "passive"))
      (node (ref "C7") (pin "2") (pinfunction "2_2") (pintype "passive"))
      (node (ref "C8") (pin "2") (pinfunction "2_2") (pintype "passive"))
      (node (ref "C9") (pin "2") (pinfunction "2_2") (pintype "passive"))
      (node (ref "F1") (pin "2") (pinfunction "2_2") (pintype "passive"))
      (node (ref "IC1") (pin "17") (pinfunction "VCC_17") (pintype "power_in"))
      (node (ref "IC1") (pin "38") (pinfunction "VCC_38") (pintype "power_in"))
      (node (ref "IC1") (pin "5") (pinfunction "VCC_5") (pintype "power_in"))
      (node (ref "IC2") (pin "1") (pinfunction "VCC_1") (pintype "power_in"))
      (node (ref "JP3") (pin "5") (pinfunction "5_5") (pintype "passive"))
      (node (ref "JTAG") (pin "4") (pinfunction "4_4") (pintype "passive"))
      (node (ref "L1") (pin "1") (pinfunction "1_1") (pintype "passive"))
      (node (ref "LS") (pin "C") (pinfunction "C_C") (pintype "passive"))
      (node (ref "R10") (pin "2") (pinfunction "2_2") (pintype "passive"))
      (node (ref "R11") (pin "2") (pinfunction "2_2") (pintype "passive"))
      (node (ref "R12") (pin "2") (pinfunction "2_2") (pintype "passive"))
      (node (ref "R13") (pin "2") (pinfunction "2_2") (pintype "passive"))
      (node (ref "R22") (pin "2") (pinfunction "2_2") (pintype "passive"))
      (node (ref "R5") (pin "2") (pinfunction "2_2") (pintype "passive"))
      (node (ref "RN1") (pin "3") (pinfunction "VCC_3") (pintype "bidirectional"))
      (node (ref "S1") (pin "3") (pinfunction "3_3") (pintype "passive"))
      (node (ref "S1") (pin "4") (pinfunction "4_4") (pintype "passive"))
      (node (ref "S2") (pin "3") (pinfunction "3_3") (pintype "passive"))
      (node (ref "S2") (pin "4") (pinfunction "4_4") (pintype "passive"))
    )
    (net (code "81") (name "unconnected-(IC3-PadREMOTE)") (class "Default")
      (node (ref "IC3") (pin "REMOTE") (pinfunction "REMOTE_REMOTE") (pintype "bidirectional"))
    )
    (net (code "82") (name "unconnected-(IC4-PadREMOTE)") (class "Default")
      (node (ref "IC4") (pin "REMOTE") (pinfunction "REMOTE_REMOTE") (pintype "bidirectional"))
    )
    (net (code "83") (name "unconnected-(JTAG-Pad7)") (class "Default")
      (node (ref "JTAG") (pin "7") (pinfunction "7_7") (pintype "passive"))
    )
    (net (code "84") (name "unconnected-(PORT_A1-Pad9)") (class "Default")
      (node (ref "PORT_A1") (pin "9") (pinfunction "9_9") (pintype "passive"))
    )
    (net (code "85") (name "unconnected-(PORT_A1-Pad10)") (class "Default")
      (node (ref "PORT_A1") (pin "10") (pinfunction "10_10") (pintype "passive"))
    )
    (net (code "86") (name "unconnected-(RN1-CTS_I-Pad2)") (class "Default")
      (node (ref "RN1") (pin "2") (pinfunction "CTS_I_2") (pintype "bidirectional"))
    )
    (net (code "87") (name "unconnected-(RN1-RTS_O-Pad6)") (class "Default")
      (node (ref "RN1") (pin "6") (pinfunction "RTS_O_6") (pintype "bidirectional"))
    )
    (net (code "88") (name "unconnected-(U$4-Pad1)") (class "Default")
      (node (ref "U$4") (pin "1") (pinfunction "1_1") (pintype "passive"))
    )
    (net (code "89") (name "unconnected-(U$4-Pad2)") (class "Default")
      (node (ref "U$4") (pin "2") (pinfunction "2_2") (pintype "passive"))
    )
    (net (code "90") (name "unconnected-(U$4-Pad3)") (class "Default")
      (node (ref "U$4") (pin "3") (pinfunction "3_3") (pintype "passive"))
    )
    (net (code "91") (name "unconnected-(U$4-Pad4)") (class "Default")
      (node (ref "U$4") (pin "4") (pinfunction "4_4") (pintype "passive"))
    )
    (net (code "92") (name "unconnected-(U$4-Pad5)") (class "Default")
      (node (ref "U$4") (pin "5") (pinfunction "5_5") (pintype "passive"))
    )
    (net (code "93") (name "unconnected-(U$4-Pad6)") (class "Default")
      (node (ref "U$4") (pin "6") (pinfunction "6_6") (pintype "passive"))
    )
    (net (code "94") (name "unconnected-(U$4-Pad7)") (class "Default")
      (node (ref "U$4") (pin "7") (pinfunction "7_7") (pintype "passive"))
    )
    (net (code "95") (name "unconnected-(U$4-Pad8)") (class "Default")
      (node (ref "U$4") (pin "8") (pinfunction "8_8") (pintype "passive"))
    )
    (net (code "96") (name "unconnected-(U$4-Pad9)") (class "Default")
      (node (ref "U$4") (pin "9") (pinfunction "9_9") (pintype "passive"))
    )
    (net (code "97") (name "unconnected-(U$4-Pad10)") (class "Default")
      (node (ref "U$4") (pin "10") (pinfunction "10_10") (pintype "passive"))
    )
    (net (code "98") (name "unconnected-(U$4-Pad11)") (class "Default")
      (node (ref "U$4") (pin "11") (pinfunction "11_11") (pintype "passive"))
    )
    (net (code "99") (name "unconnected-(U$4-Pad12)") (class "Default")
      (node (ref "U$4") (pin "12") (pinfunction "12_12") (pintype "passive"))
    )
    (net (code "100") (name "unconnected-(U$4-Pad13)") (class "Default")
      (node (ref "U$4") (pin "13") (pinfunction "13_13") (pintype "passive"))
    )
    (net (code "101") (name "unconnected-(U$4-Pad14)") (class "Default")
      (node (ref "U$4") (pin "14") (pinfunction "14_14") (pintype "passive"))
    )
    (net (code "102") (name "unconnected-(U$4-Pad16)") (class "Default")
      (node (ref "U$4") (pin "16") (pinfunction "16_16") (pintype "passive"))
    )
    (net (code "103") (name "unconnected-(U$4-Pad17)") (class "Default")
      (node (ref "U$4") (pin "17") (pinfunction "17_17") (pintype "passive"))
    )
    (net (code "104") (name "unconnected-(U$4-Pad19)") (class "Default")
      (node (ref "U$4") (pin "19") (pinfunction "19_19") (pintype "passive"))
    )
    (net (code "105") (name "unconnected-(U$4-Pad20)") (class "Default")
      (node (ref "U$4") (pin "20") (pinfunction "20_20") (pintype "passive"))
    )
    (net (code "106") (name "unconnected-(U$4-Pad21)") (class "Default")
      (node (ref "U$4") (pin "21") (pinfunction "21_21") (pintype "passive"))
    )
    (net (code "107") (name "unconnected-(U$4-Pad22)") (class "Default")
      (node (ref "U$4") (pin "22") (pinfunction "22_22") (pintype "passive"))
    )
    (net (code "108") (name "unconnected-(U$4-Pad23)") (class "Default")
      (node (ref "U$4") (pin "23") (pinfunction "23_23") (pintype "passive"))
    )
    (net (code "109") (name "unconnected-(U$4-Pad24)") (class "Default")
      (node (ref "U$4") (pin "24") (pinfunction "24_24") (pintype "passive"))
    )
    (net (code "110") (name "unconnected-(U$4-Pad25)") (class "Default")
      (node (ref "U$4") (pin "25") (pinfunction "25_25") (pintype "passive"))
    )
    (net (code "111") (name "unconnected-(U$4-Pad26)") (class "Default")
      (node (ref "U$4") (pin "26") (pinfunction "26_26") (pintype "passive"))
    )
    (net (code "112") (name "unconnected-(U$4-Pad27)") (class "Default")
      (node (ref "U$4") (pin "27") (pinfunction "27_27") (pintype "passive"))
    )
    (net (code "113") (name "unconnected-(U$4-Pad28)") (class "Default")
      (node (ref "U$4") (pin "28") (pinfunction "28_28") (pintype "passive"))
    )
    (net (code "114") (name "unconnected-(U$4-Pad29)") (class "Default")
      (node (ref "U$4") (pin "29") (pinfunction "29_29") (pintype "passive"))
    )
    (net (code "115") (name "unconnected-(U$4-Pad30)") (class "Default")
      (node (ref "U$4") (pin "30") (pinfunction "30_30") (pintype "passive"))
    )
    (net (code "116") (name "unconnected-(U$4-Pad33)") (class "Default")
      (node (ref "U$4") (pin "33") (pinfunction "33_33") (pintype "passive"))
    )
    (net (code "117") (name "unconnected-(U$4-Pad34)") (class "Default")
      (node (ref "U$4") (pin "34") (pinfunction "34_34") (pintype "passive"))
    )
    (net (code "118") (name "unconnected-(X1-Pad2)") (class "Default")
      (node (ref "X1") (pin "2") (pinfunction "2_2") (pintype "passive"))
    )
    (net (code "119") (name "unconnected-(X1-Pad3)") (class "Default")
      (node (ref "X1") (pin "3") (pinfunction "3_3") (pintype "passive"))
    )
  )
)
